# V2.net
KiCad netlist of a schematic drawn in EAGLE
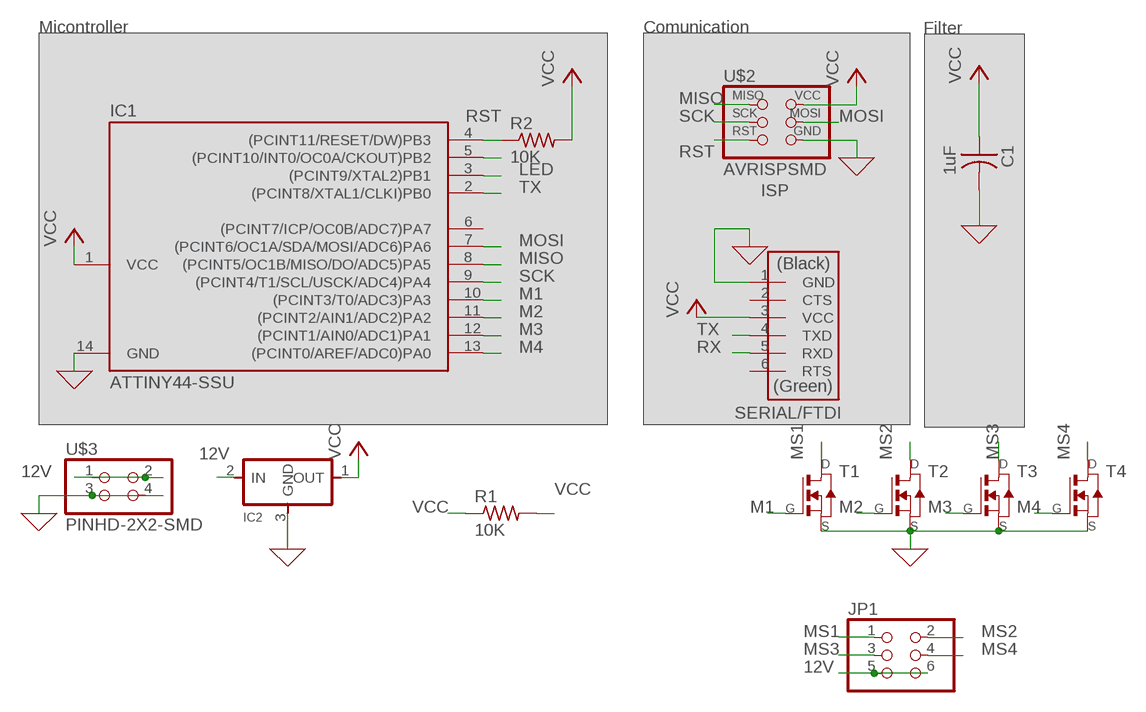
[diagram p0: schematic, sheet 1]

(export (version "E")
  (design (tool "Eeschema 10.0.6"))
  (components
    (comp (ref "C1")
      (value "1uF")
      (footprint "eagle-import:C1206FAB")
      (libsource (lib "eagle-import") (part "CAP-US1206FAB"))
    )
    (comp (ref "IC1")
      (value "ATTINY44-SSU")
      (footprint "eagle-import:SOIC14")
      (libsource (lib "eagle-import") (part "ATTINY44-SSU"))
    )
    (comp (ref "IC2")
      (value "REGULATORSOT23")
      (footprint "eagle-import:SOT23")
      (libsource (lib "eagle-import") (part "REGULATORSOT23"))
    )
    (comp (ref "JP1")
      (value "PINHD-2X3-SMD")
      (footprint "eagle-import:2X03SMD")
      (libsource (lib "eagle-import") (part "PINHD-2X3-SMD"))
    )
    (comp (ref "R1")
      (value "10K")
      (footprint "eagle-import:R1206FAB")
      (libsource (lib "eagle-import") (part "RES-US1206FAB"))
    )
    (comp (ref "R2")
      (value "10K")
      (footprint "eagle-import:R1206FAB")
      (libsource (lib "eagle-import") (part "RES-US1206FAB"))
    )
    (comp (ref "T1")
      (value "NMOSFETSOT23")
      (footprint "eagle-import:SOT-23")
      (libsource (lib "eagle-import") (part "NMOSFETSOT23"))
    )
    (comp (ref "T2")
      (value "NMOSFETSOT23")
      (footprint "eagle-import:SOT-23")
      (libsource (lib "eagle-import") (part "NMOSFETSOT23"))
    )
    (comp (ref "T3")
      (value "NMOSFETSOT23")
      (footprint "eagle-import:SOT-23")
      (libsource (lib "eagle-import") (part "NMOSFETSOT23"))
    )
    (comp (ref "T4")
      (value "NMOSFETSOT23")
      (footprint "eagle-import:SOT-23")
      (libsource (lib "eagle-import") (part "NMOSFETSOT23"))
    )
    (comp (ref "U$1")
      (value "FTDI-SMD-HEADER")
      (footprint "eagle-import:1X06SMD")
      (libsource (lib "eagle-import") (part "FTDI-SMD-HEADER"))
    )
    (comp (ref "U$2")
      (value "AVRISPSMD")
      (footprint "eagle-import:2X03SMD")
      (libsource (lib "eagle-import") (part "AVRISPSMD"))
    )
    (comp (ref "U$3")
      (value "PINHD-2X2-SMD")
      (footprint "eagle-import:2X02SMD")
      (libsource (lib "eagle-import") (part "PINHD-2X2-SMD"))
    )
  )
  (nets
    (net (code "1") (name "/12V") (class "Default")
      (node (ref "IC2") (pin "2") (pinfunction "IN_2") (pintype "bidirectional"))
      (node (ref "JP1") (pin "5") (pinfunction "5_5") (pintype "passive"))
      (node (ref "JP1") (pin "6") (pinfunction "6_6") (pintype "passive"))
      (node (ref "U$3") (pin "1") (pinfunction "1_1") (pintype "passive"))
      (node (ref "U$3") (pin "2") (pinfunction "2_2") (pintype "passive"))
    )
    (net (code "2") (name "/LED") (class "Default")
      (node (ref "IC1") (pin "3") (pinfunction "(PCINT9/XTAL2)PB1_3") (pintype "bidirectional"))
    )
    (net (code "3") (name "/M1") (class "Default")
      (node (ref "IC1") (pin "10") (pinfunction "(PCINT3/T0/ADC3)PA3_10") (pintype "bidirectional"))
      (node (ref "T1") (pin "3") (pinfunction "G_3") (pintype "passive"))
    )
    (net (code "4") (name "/M2") (class "Default")
      (node (ref "IC1") (pin "11") (pinfunction "(PCINT2/AIN1/ADC2)PA2_11") (pintype "bidirectional"))
      (node (ref "T2") (pin "3") (pinfunction "G_3") (pintype "passive"))
    )
    (net (code "5") (name "/M3") (class "Default")
      (node (ref "IC1") (pin "12") (pinfunction "(PCINT1/AIN0/ADC1)PA1_12") (pintype "bidirectional"))
      (node (ref "T3") (pin "3") (pinfunction "G_3") (pintype "passive"))
    )
    (net (code "6") (name "/M4") (class "Default")
      (node (ref "IC1") (pin "13") (pinfunction "(PCINT0/AREF/ADC0)PA0_13") (pintype "bidirectional"))
      (node (ref "T4") (pin "3") (pinfunction "G_3") (pintype "passive"))
    )
    (net (code "7") (name "/MISO") (class "Default")
      (node (ref "IC1") (pin "8") (pinfunction "(PCINT5/OC1B/MISO/DO/ADC5)PA5_8") (pintype "bidirectional"))
      (node (ref "U$2") (pin "1") (pinfunction "MISO_1") (pintype "passive"))
    )
    (net (code "8") (name "/MOSI") (class "Default")
      (node (ref "IC1") (pin "7") (pinfunction "(PCINT6/OC1A/SDA/MOSI/ADC6)PA6_7") (pintype "bidirectional"))
      (node (ref "U$2") (pin "4") (pinfunction "MOSI_4") (pintype "passive"))
    )
    (net (code "9") (name "/MS1") (class "Default")
      (node (ref "JP1") (pin "1") (pinfunction "1_1") (pintype "passive"))
      (node (ref "T1") (pin "1") (pinfunction "D_1") (pintype "passive"))
    )
    (net (code "10") (name "/MS2") (class "Default")
      (node (ref "JP1") (pin "2") (pinfunction "2_2") (pintype "passive"))
      (node (ref "T2") (pin "1") (pinfunction "D_1") (pintype "passive"))
    )
    (net (code "11") (name "/MS3") (class "Default")
      (node (ref "JP1") (pin "3") (pinfunction "3_3") (pintype "passive"))
      (node (ref "T3") (pin "1") (pinfunction "D_1") (pintype "passive"))
    )
    (net (code "12") (name "/MS4") (class "Default")
      (node (ref "JP1") (pin "4") (pinfunction "4_4") (pintype "passive"))
      (node (ref "T4") (pin "1") (pinfunction "D_1") (pintype "passive"))
    )
    (net (code "13") (name "/RST") (class "Default")
      (node (ref "IC1") (pin "4") (pinfunction "(PCINT11/RESET/DW)PB3_4") (pintype "bidirectional"))
      (node (ref "R2") (pin "1") (pinfunction "1_1") (pintype "passive"))
      (node (ref "U$2") (pin "5") (pinfunction "RST_5") (pintype "passive"))
    )
    (net (code "14") (name "/RX") (class "Default")
      (node (ref "U$1") (pin "5") (pinfunction "RXD_5") (pintype "bidirectional"))
    )
    (net (code "15") (name "/SCK") (class "Default")
      (node (ref "IC1") (pin "9") (pinfunction "(PCINT4/T1/SCL/USCK/ADC4)PA4_9") (pintype "bidirectional"))
      (node (ref "U$2") (pin "3") (pinfunction "SCK_3") (pintype "passive"))
    )
    (net (code "16") (name "/TX") (class "Default")
      (node (ref "IC1") (pin "2") (pinfunction "(PCINT8/XTAL1/CLKI)PB0_2") (pintype "bidirectional"))
      (node (ref "U$1") (pin "4") (pinfunction "TXD_4") (pintype "bidirectional"))
    )
    (net (code "17") (name "GND") (class "Default")
      (node (ref "C1") (pin "2") (pinfunction "2_2") (pintype "passive"))
      (node (ref "IC1") (pin "14") (pinfunction "GND_14") (pintype "power_in"))
      (node (ref "IC2") (pin "3") (pinfunction "GND_3") (pintype "bidirectional"))
      (node (ref "T1") (pin "2") (pinfunction "S_2") (pintype "passive"))
      (node (ref "T2") (pin "2") (pinfunction "S_2") (pintype "passive"))
      (node (ref "T3") (pin "2") (pinfunction "S_2") (pintype "passive"))
      (node (ref "T4") (pin "2") (pinfunction "S_2") (pintype "passive"))
      (node (ref "U$1") (pin "1") (pinfunction "GND_1") (pintype "bidirectional"))
      (node (ref "U$2") (pin "6") (pinfunction "GND_6") (pintype "passive"))
      (node (ref "U$3") (pin "3") (pinfunction "3_3") (pintype "passive"))
      (node (ref "U$3") (pin "4") (pinfunction "4_4") (pintype "passive"))
    )
    (net (code "18") (name "VCC") (class "Default")
      (node (ref "C1") (pin "1") (pinfunction "1_1") (pintype "passive"))
      (node (ref "IC1") (pin "1") (pinfunction "VCC_1") (pintype "power_in"))
      (node (ref "IC2") (pin "1") (pinfunction "OUT_1") (pintype "bidirectional"))
      (node (ref "R1") (pin "1") (pinfunction "1_1") (pintype "passive"))
      (node (ref "R1") (pin "2") (pinfunction "2_2") (pintype "passive"))
      (node (ref "R2") (pin "2") (pinfunction "2_2") (pintype "passive"))
      (node (ref "U$1") (pin "3") (pinfunction "VCC_3") (pintype "bidirectional"))
      (node (ref "U$2") (pin "2") (pinfunction "VCC_2") (pintype "passive"))
    )
    (net (code "19") (name "unconnected-(IC1-(PCINT7{slash}ICP{slash}OC0B{slash}ADC7)PA7-Pad6)") (class "Default")
      (node (ref "IC1") (pin "6") (pinfunction "(PCINT7/ICP/OC0B/ADC7)PA7_6") (pintype "bidirectional"))
    )
    (net (code "20") (name "unconnected-(IC1-(PCINT10{slash}INT0{slash}OC0A{slash}CKOUT)PB2-Pad5)") (class "Default")
      (node (ref "IC1") (pin "5") (pinfunction "(PCINT10/INT0/OC0A/CKOUT)PB2_5") (pintype "bidirectional"))
    )
    (net (code "21") (name "unconnected-(U$1-CTS-Pad2)") (class "Default")
      (node (ref "U$1") (pin "2") (pinfunction "CTS_2") (pintype "bidirectional"))
    )
    (net (code "22") (name "unconnected-(U$1-RTS-Pad6)") (class "Default")
      (node (ref "U$1") (pin "6") (pinfunction "RTS_6") (pintype "bidirectional"))
    )
  )
)
